# Burn_Wires.net
KiCad netlist of a schematic drawn in Altium Designer
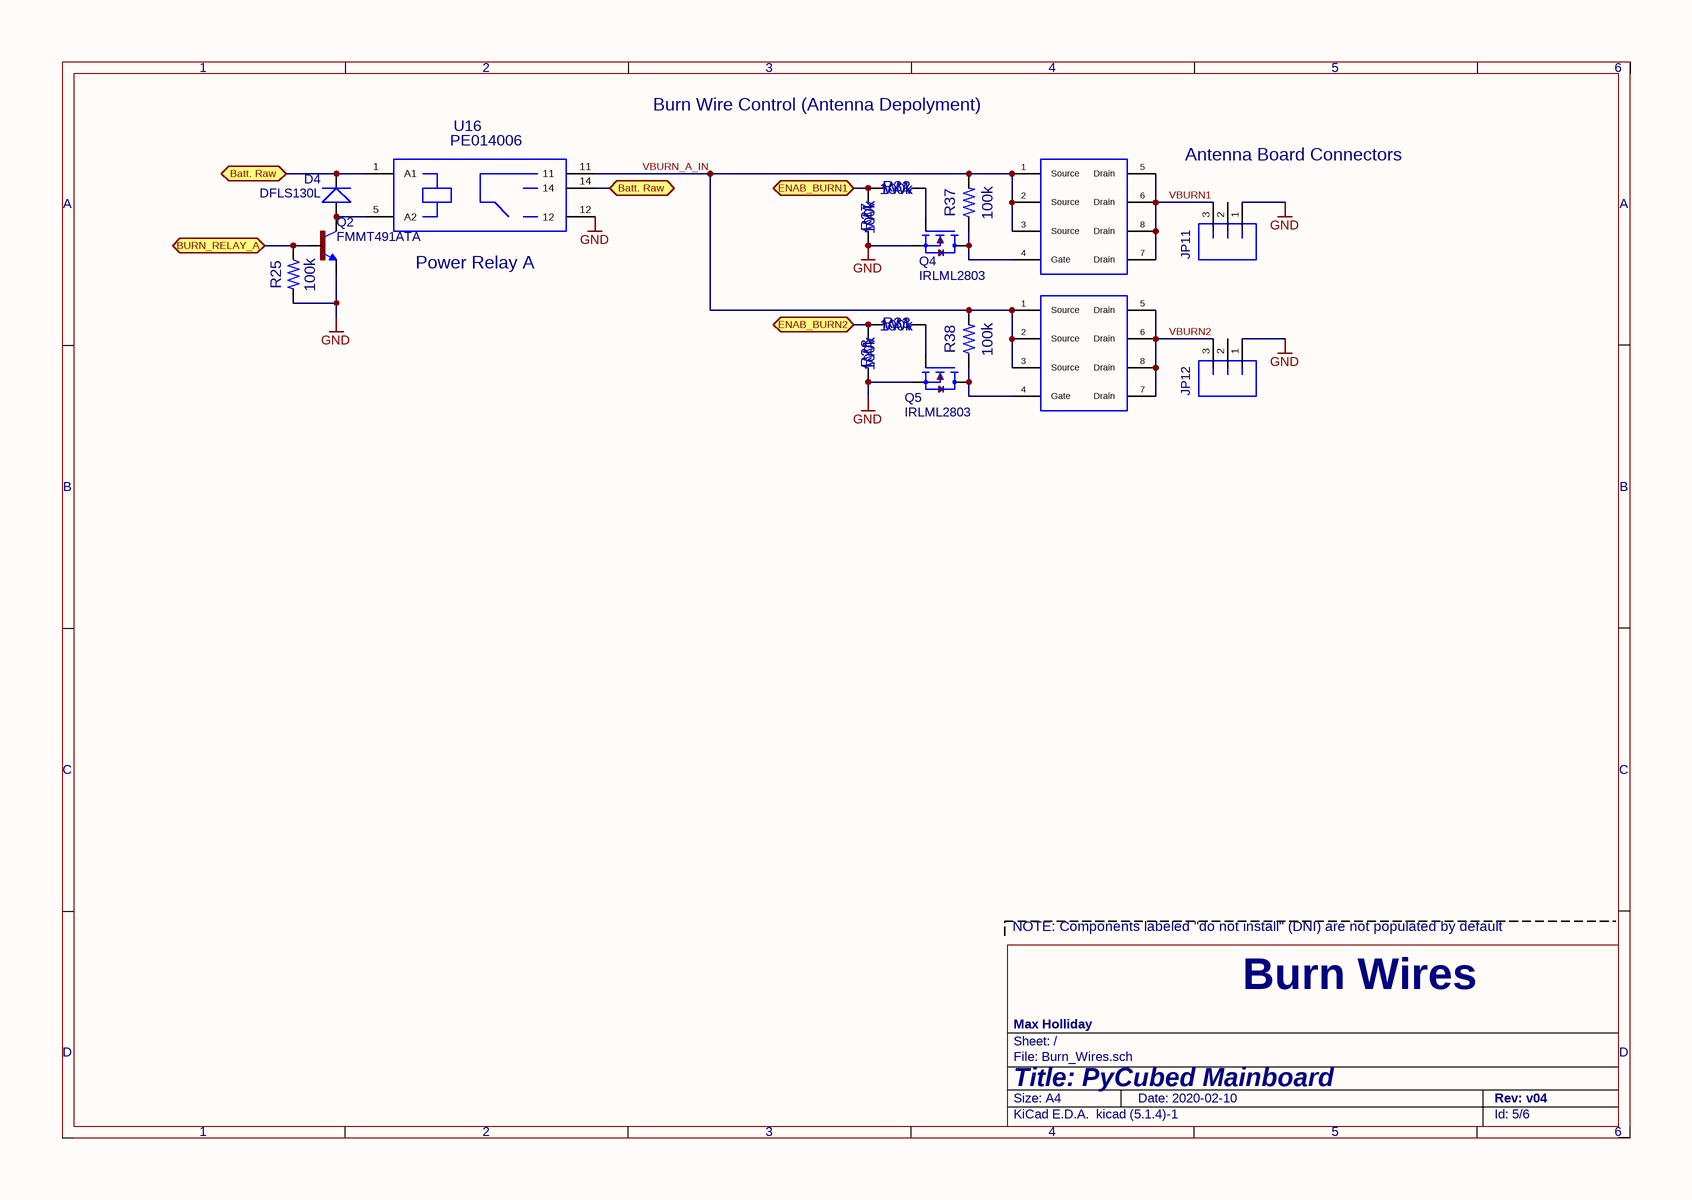
[diagram p0: Burn_Wires.SchDoc]

(export (version "E")
  (design (tool "Eeschema 10.0.6"))
  (components
    (comp (ref "D4")
      (value "DFLS130L")
      (footprint "PWRDI-123")
      (fields (field (name "Comment") "SBR2A40P1Q-7"))
      (libsource (lib "mainboard_1") (part "DFLS130L"))
    )
    (comp (ref "JP11")
      (value "Conn_01x03")
      (footprint "MOLEX-1X3_LOCK")
      (libsource (lib "mainboard_1") (part "M03POLAR_LOCK"))
    )
    (comp (ref "JP12")
      (value "Conn_01x03")
      (footprint "MOLEX-1X3_LOCK")
      (libsource (lib "mainboard_1") (part "M03POLAR_LOCK"))
    )
    (comp (ref "Q2") (value "FMMT491ATA") (footprint "SOT23") (libsource (lib "mainboard_1") (part "BC846")))
    (comp (ref "Q4")
      (value "IRLML2803")
      (footprint "SOT-23")
      (libsource (lib "mainboard_1") (part "IRLML2803TRPBF"))
    )
    (comp (ref "Q5")
      (value "IRLML2803")
      (footprint "SOT-23")
      (libsource (lib "mainboard_1") (part "IRLML2803TRPBF"))
    )
    (comp (ref "R25")
      (value "100k")
      (footprint "R_0603_1608Metric")
      (fields (field (name "MPN") "RC0603JR-07100KL"))
      (libsource (lib "mainboard_1") (part "RESISTOR0603"))
    )
    (comp (ref "R27")
      (value "100k")
      (footprint "R_0603_1608Metric")
      (fields (field (name "MPN") "RC0603JR-07100KL"))
      (libsource (lib "mainboard_1") (part "RESISTOR0603"))
    )
    (comp (ref "R28")
      (value "100k")
      (footprint "R_0603_1608Metric")
      (fields (field (name "MPN") "RC0603JR-07100KL"))
      (libsource (lib "mainboard_1") (part "RESISTOR0603"))
    )
    (comp (ref "R32")
      (value "100k")
      (footprint "R_0603_1608Metric")
      (fields (field (name "MPN") "RC0603JR-07100KL"))
      (libsource (lib "mainboard_1") (part "RESISTOR0603"))
    )
    (comp (ref "R33")
      (value "100k")
      (footprint "R_0603_1608Metric")
      (fields (field (name "MPN") "RC0603JR-07100KL"))
      (libsource (lib "mainboard_1") (part "RESISTOR0603"))
    )
    (comp (ref "R37")
      (value "100k")
      (footprint "R_0603_1608Metric")
      (fields (field (name "MPN") "RC0603JR-07100KL"))
      (libsource (lib "mainboard_1") (part "RESISTOR0603"))
    )
    (comp (ref "R38")
      (value "100k")
      (footprint "R_0603_1608Metric")
      (fields (field (name "MPN") "RC0603JR-07100KL"))
      (libsource (lib "mainboard_1") (part "RESISTOR0603"))
    )
    (comp (ref "U16")
      (value "PE014006")
      (footprint "RELAY5-PE_CO")
      (fields (field (name "MPN") "PE014006 TE"))
      (libsource (lib "mainboard_1") (part "PE014005"))
    )
    (comp (ref "U18")
      (value "NDS8434")
      (footprint "NDS8434")
      (fields (field (name "MPN") "IRF7404TRPBF"))
      (libsource (lib "mainboard_1") (part "NDS8434"))
    )
    (comp (ref "U19")
      (value "NDS8434")
      (footprint "NDS8434")
      (fields (field (name "MPN") "IRF7404TRPBF"))
      (libsource (lib "mainboard_1") (part "NDS8434"))
    )
  )
  (nets
    (net (code "1") (name "/BURN_RELAY_A") (class "Default")
      (node (ref "Q2") (pin "1") (pinfunction "B_1") (pintype "passive"))
      (node (ref "R25") (pin "1") (pinfunction "1_1") (pintype "passive"))
    )
    (net (code "2") (name "/Batt. Raw") (class "Default")
      (node (ref "D4") (pin "C") (pinfunction "C_C") (pintype "passive"))
      (node (ref "U16") (pin "1") (pinfunction "A1_1") (pintype "passive"))
      (node (ref "U16") (pin "14") (pinfunction "14_14") (pintype "passive"))
    )
    (net (code "3") (name "/ENAB_BURN1") (class "Default")
      (node (ref "R27") (pin "1") (pinfunction "1_1") (pintype "passive"))
      (node (ref "R32") (pin "2") (pinfunction "2_2") (pintype "passive"))
    )
    (net (code "4") (name "/ENAB_BURN2") (class "Default")
      (node (ref "R28") (pin "1") (pinfunction "1_1") (pintype "passive"))
      (node (ref "R33") (pin "2") (pinfunction "2_2") (pintype "passive"))
    )
    (net (code "5") (name "/VBURN1") (class "Default")
      (node (ref "JP11") (pin "3") (pinfunction "3_3") (pintype "passive"))
      (node (ref "U18") (pin "5") (pinfunction "Drain_5") (pintype "passive"))
      (node (ref "U18") (pin "6") (pinfunction "Drain_6") (pintype "passive"))
      (node (ref "U18") (pin "7") (pinfunction "Drain_7") (pintype "passive"))
      (node (ref "U18") (pin "8") (pinfunction "Drain_8") (pintype "passive"))
    )
    (net (code "6") (name "/VBURN2") (class "Default")
      (node (ref "JP12") (pin "3") (pinfunction "3_3") (pintype "passive"))
      (node (ref "U19") (pin "5") (pinfunction "Drain_5") (pintype "passive"))
      (node (ref "U19") (pin "6") (pinfunction "Drain_6") (pintype "passive"))
      (node (ref "U19") (pin "7") (pinfunction "Drain_7") (pintype "passive"))
      (node (ref "U19") (pin "8") (pinfunction "Drain_8") (pintype "passive"))
    )
    (net (code "7") (name "/VBURN_A_IN") (class "Default")
      (node (ref "R37") (pin "2") (pinfunction "2_2") (pintype "passive"))
      (node (ref "R38") (pin "2") (pinfunction "2_2") (pintype "passive"))
      (node (ref "U16") (pin "11") (pinfunction "11_11") (pintype "passive"))
      (node (ref "U18") (pin "1") (pinfunction "Source_1") (pintype "passive"))
      (node (ref "U18") (pin "2") (pinfunction "Source_2") (pintype "passive"))
      (node (ref "U18") (pin "3") (pinfunction "Source_3") (pintype "passive"))
      (node (ref "U19") (pin "1") (pinfunction "Source_1") (pintype "passive"))
      (node (ref "U19") (pin "2") (pinfunction "Source_2") (pintype "passive"))
      (node (ref "U19") (pin "3") (pinfunction "Source_3") (pintype "passive"))
    )
    (net (code "8") (name "GND") (class "Default")
      (node (ref "JP11") (pin "1") (pinfunction "1_1") (pintype "passive"))
      (node (ref "JP12") (pin "1") (pinfunction "1_1") (pintype "passive"))
      (node (ref "Q2") (pin "2") (pinfunction "E_2") (pintype "passive"))
      (node (ref "Q4") (pin "2") (pinfunction "S_2") (pintype "passive"))
      (node (ref "Q5") (pin "2") (pinfunction "S_2") (pintype "passive"))
      (node (ref "R25") (pin "2") (pinfunction "2_2") (pintype "passive"))
      (node (ref "R27") (pin "2") (pinfunction "2_2") (pintype "passive"))
      (node (ref "R28") (pin "2") (pinfunction "2_2") (pintype "passive"))
      (node (ref "U16") (pin "12") (pinfunction "12_12") (pintype "passive"))
    )
    (net (code "9") (name "Net-(Q2-C)") (class "Default")
      (node (ref "D4") (pin "A") (pinfunction "A_A") (pintype "passive"))
      (node (ref "Q2") (pin "3") (pinfunction "C_3") (pintype "passive"))
      (node (ref "U16") (pin "5") (pinfunction "A2_5") (pintype "passive"))
    )
    (net (code "10") (name "Net-(Q4-D)") (class "Default")
      (node (ref "Q4") (pin "3") (pinfunction "D_3") (pintype "passive"))
      (node (ref "R37") (pin "1") (pinfunction "1_1") (pintype "passive"))
      (node (ref "U18") (pin "4") (pinfunction "Gate_4") (pintype "passive"))
    )
    (net (code "11") (name "Net-(Q4-G)") (class "Default")
      (node (ref "Q4") (pin "1") (pinfunction "G_1") (pintype "passive"))
      (node (ref "R32") (pin "1") (pinfunction "1_1") (pintype "passive"))
    )
    (net (code "12") (name "Net-(Q5-D)") (class "Default")
      (node (ref "Q5") (pin "3") (pinfunction "D_3") (pintype "passive"))
      (node (ref "R38") (pin "1") (pinfunction "1_1") (pintype "passive"))
      (node (ref "U19") (pin "4") (pinfunction "Gate_4") (pintype "passive"))
    )
    (net (code "13") (name "Net-(Q5-G)") (class "Default")
      (node (ref "Q5") (pin "1") (pinfunction "G_1") (pintype "passive"))
      (node (ref "R33") (pin "1") (pinfunction "1_1") (pintype "passive"))
    )
    (net (code "14") (name "unconnected-(JP11-Pad2)") (class "Default")
      (node (ref "JP11") (pin "2") (pinfunction "2_2") (pintype "passive"))
    )
    (net (code "15") (name "unconnected-(JP12-Pad2)") (class "Default")
      (node (ref "JP12") (pin "2") (pinfunction "2_2") (pintype "passive"))
    )
  )
)
